# Power.net
KiCad netlist of a schematic drawn in Altium Designer
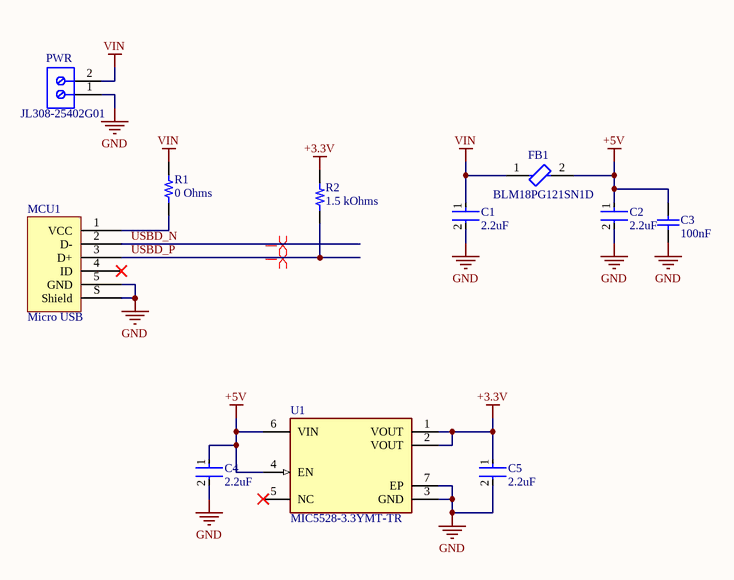
[diagram p0: Power.SchDoc]

(export (version "E")
  (design (tool "Eeschema 10.0.6"))
  (components
    (comp (ref "C1")
      (value "2.2uF")
      (footprint "FP-CL10-IPC_A")
      (description "Cap Ceramic 2.2uF 16V X5R ±10% Pad SMD 0603 +85°C T/R")
      (fields (field (name "TOLERANCE") "10%") (field (name "VOLTAGE") "16V"))
      (libsource (lib "Altium Content Vault") (part "b4654b650e69147ec39a6b967a45e02"))
    )
    (comp (ref "C2")
      (value "2.2uF")
      (footprint "FP-CL10-IPC_A")
      (description "Cap Ceramic 2.2uF 16V X5R ±10% Pad SMD 0603 +85°C T/R")
      (fields (field (name "TOLERANCE") "10%") (field (name "VOLTAGE") "16V"))
      (libsource (lib "Altium Content Vault") (part "b4654b650e69147ec39a6b967a45e02"))
    )
    (comp (ref "C3")
      (value "100nF")
      (footprint "CAPC1050X55X23ML05T13")
      (description "Chip Capacitor, 100 nF, +/- 10%, 16 V, -55 to 125 degC, 0402 (1005 Metric), RoHS, Tape and Reel")
      (fields (field (name "MANUFACTURER") "Samsung Electro-Mechanics"))
      (libsource (lib "Altium Content Vault") (part "CAP-NP-2"))
    )
    (comp (ref "C4")
      (value "2.2uF")
      (footprint "FP-CL10-IPC_A")
      (description "Cap Ceramic 2.2uF 16V X5R ±10% Pad SMD 0603 +85°C T/R")
      (fields (field (name "TOLERANCE") "10%") (field (name "VOLTAGE") "16V"))
      (libsource (lib "Altium Content Vault") (part "b4654b650e69147ec39a6b967a45e02"))
    )
    (comp (ref "C5")
      (value "2.2uF")
      (footprint "FP-CL10-IPC_A")
      (description "Cap Ceramic 2.2uF 16V X5R ±10% Pad SMD 0603 +85°C T/R")
      (fields (field (name "TOLERANCE") "10%") (field (name "VOLTAGE") "16V"))
      (libsource (lib "Altium Content Vault") (part "b4654b650e69147ec39a6b967a45e02"))
    )
    (comp (ref "FB1")
      (value "BLM18PG121SN1D")
      (footprint "FP-BLM18-0_15-t0_8-IPC_A")
      (description "Chip Ferrite Bead, 0603, 120Ω @ 100MHz, 0.05Ω, 25%, 2A")
      (fields (field (name "TOLERANCE") "25%"))
      (libsource (lib "Altium Content Vault") (part "5f30dd21d616792df468990f7003faa"))
    )
    (comp (ref "MCU1")
      (value "Micro USB")
      (footprint "FCI USB 10118193-0001LF")
      (description "CONN RCPT USB2.0 MICRO B SMD R/A")
      (fields
        (field (name "PART NUMBER") "10118193-0001LF")
        (field (name "MANUFACTURER") "Amphenol ICC (FCI)")
      )
      (libsource (lib "Celestial Altium Library - altium_library") (part "USB 2.0 Type B Micro"))
    )
    (comp (ref "PWR")
      (value "JL308-25402G01")
      (footprint "691210910002")
      (description "Use comment for part number")
      (libsource (lib "Altium Content Vault") (part "TBL - 1R - 02P - Screw"))
    )
    (comp (ref "R1")
      (value "0 Ohms")
      (footprint "RES 0805_2012")
      (description "0805 0 ohm - use 0805W8F0000T5E")
      (fields
        (field (name "PART NUMBER") "TLRZ2ATTD")
        (field (name "MANUFACTURER") "KOA Speer Electronics, Inc.")
      )
      (libsource (lib "Celestial Altium Library - altium_library") (part "Resistor"))
    )
    (comp (ref "R2")
      (value "1.5 kOhms")
      (footprint "RES 0402_1005")
      (description "RES 1.5K OHM 1% 1/16W 0402")
      (fields
        (field (name "PART NUMBER") "RMCF0402FT1K50")
        (field (name "MANUFACTURER") "Stackpole Electronics Inc")
      )
      (libsource (lib "Celestial Altium Library - altium_library") (part "Resistor"))
    )
    (comp (ref "U1")
      (value "MIC5528-3.3YMT-TR")
      (footprint "FP-TDFN1212-6LD-PL-1-MFG")
      (description "IC REG LINEAR 3.3V 500MA 6TDFN")
      (libsource (lib "Altium Content Vault") (part "234cda9694c1f3435defb6efdead5b5"))
    )
  )
  (nets
    (net (code "1") (name "+3.3V") (class "Default")
      (node (ref "C5") (pin "1") (pinfunction "1_1") (pintype "passive"))
      (node (ref "R2") (pin "2") (pinfunction "2_2") (pintype "passive"))
      (node (ref "U1") (pin "1") (pinfunction "VOUT_1") (pintype "passive"))
      (node (ref "U1") (pin "2") (pinfunction "VOUT_2") (pintype "passive"))
    )
    (net (code "2") (name "+5V") (class "Default")
      (node (ref "C2") (pin "1") (pinfunction "1_1") (pintype "passive"))
      (node (ref "C3") (pin "2") (pinfunction "2_2") (pintype "passive"))
      (node (ref "C4") (pin "1") (pinfunction "1_1") (pintype "passive"))
      (node (ref "FB1") (pin "2") (pinfunction "2_2") (pintype "passive"))
      (node (ref "U1") (pin "4") (pinfunction "EN_4") (pintype "input"))
      (node (ref "U1") (pin "6") (pinfunction "VIN_6") (pintype "power_in"))
    )
    (net (code "3") (name "/USBD_N") (class "Default")
      (node (ref "MCU1") (pin "2") (pinfunction "D-_2") (pintype "passive"))
    )
    (net (code "4") (name "/USBD_P") (class "Default")
      (node (ref "MCU1") (pin "3") (pinfunction "D+_3") (pintype "passive"))
      (node (ref "R2") (pin "1") (pinfunction "1_1") (pintype "passive"))
    )
    (net (code "5") (name "GND") (class "Default")
      (node (ref "C1") (pin "2") (pinfunction "2_2") (pintype "passive"))
      (node (ref "C2") (pin "2") (pinfunction "2_2") (pintype "passive"))
      (node (ref "C3") (pin "1") (pinfunction "1_1") (pintype "passive"))
      (node (ref "C4") (pin "2") (pinfunction "2_2") (pintype "passive"))
      (node (ref "C5") (pin "2") (pinfunction "2_2") (pintype "passive"))
      (node (ref "MCU1") (pin "5") (pinfunction "GND_5") (pintype "passive"))
      (node (ref "MCU1") (pin "S") (pinfunction "Shield_S") (pintype "passive"))
      (node (ref "PWR") (pin "1") (pinfunction "1_1") (pintype "passive"))
      (node (ref "U1") (pin "3") (pinfunction "GND_3") (pintype "power_in"))
      (node (ref "U1") (pin "7") (pinfunction "EP_7") (pintype "passive"))
    )
    (net (code "6") (name "Net-(MCU1-VCC)") (class "Default")
      (node (ref "MCU1") (pin "1") (pinfunction "VCC_1") (pintype "passive"))
      (node (ref "R1") (pin "2") (pinfunction "2_2") (pintype "passive"))
    )
    (net (code "7") (name "VIN") (class "Default")
      (node (ref "C1") (pin "1") (pinfunction "1_1") (pintype "passive"))
      (node (ref "FB1") (pin "1") (pinfunction "1_1") (pintype "passive"))
      (node (ref "PWR") (pin "2") (pinfunction "2_2") (pintype "passive"))
      (node (ref "R1") (pin "1") (pinfunction "1_1") (pintype "passive"))
    )
    (net (code "8") (name "unconnected-(MCU1-ID-Pad4)") (class "Default")
      (node (ref "MCU1") (pin "4") (pinfunction "ID_4") (pintype "passive+no_connect"))
    )
    (net (code "9") (name "unconnected-(U1-NC-Pad5)") (class "Default")
      (node (ref "U1") (pin "5") (pinfunction "NC_5") (pintype "passive+no_connect"))
    )
  )
)
